# swichboard.net
KiCad netlist of a schematic drawn in EAGLE
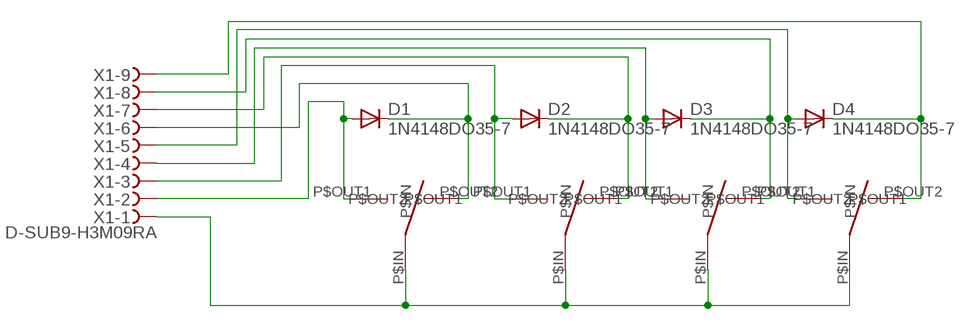
[diagram p0: schematic, sheet 1]

(export (version "E")
  (design (tool "Eeschema 10.0.6"))
  (components
    (comp (ref "D1")
      (value "1N4148DO35-7")
      (footprint "eagle-import:DO35-7")
      (libsource (lib "eagle-import") (part "1N4148DO35-7"))
    )
    (comp (ref "D2")
      (value "1N4148DO35-7")
      (footprint "eagle-import:DO35-7")
      (libsource (lib "eagle-import") (part "1N4148DO35-7"))
    )
    (comp (ref "D3")
      (value "1N4148DO35-7")
      (footprint "eagle-import:DO35-7")
      (libsource (lib "eagle-import") (part "1N4148DO35-7"))
    )
    (comp (ref "D4")
      (value "1N4148DO35-7")
      (footprint "eagle-import:DO35-7")
      (libsource (lib "eagle-import") (part "1N4148DO35-7"))
    )
    (comp (ref "U$1")
      (value "MS500E")
      (footprint "eagle-import:MS500E")
      (libsource (lib "eagle-import") (part "MS500E"))
    )
    (comp (ref "U$2")
      (value "MS500E")
      (footprint "eagle-import:MS500E")
      (libsource (lib "eagle-import") (part "MS500E"))
    )
    (comp (ref "U$3")
      (value "MS500E")
      (footprint "eagle-import:MS500E")
      (libsource (lib "eagle-import") (part "MS500E"))
    )
    (comp (ref "U$4")
      (value "MS500E")
      (footprint "eagle-import:MS500E")
      (libsource (lib "eagle-import") (part "MS500E"))
    )
    (comp (ref "X1")
      (value "D-SUB9-H3M09RA")
      (footprint "eagle-import:H3M09RA")
      (libsource (lib "eagle-import") (part "D-SUB9-H3M09RA"))
    )
  )
  (nets
    (net (code "1") (name "Net-(X1A-F)") (class "Default")
      (node (ref "U$1") (pin "P$IN") (pinfunction "P$IN_P$IN") (pintype "bidirectional"))
      (node (ref "U$2") (pin "P$IN") (pinfunction "P$IN_P$IN") (pintype "bidirectional"))
      (node (ref "U$3") (pin "P$IN") (pinfunction "P$IN_P$IN") (pintype "bidirectional"))
      (node (ref "U$4") (pin "P$IN") (pinfunction "P$IN_P$IN") (pintype "bidirectional"))
      (node (ref "X1") (pin "1") (pinfunction "F_1") (pintype "passive"))
    )
    (net (code "2") (name "Net-(X1B-F)") (class "Default")
      (node (ref "D1") (pin "A") (pinfunction "A_A") (pintype "passive"))
      (node (ref "U$1") (pin "P$OUT1") (pinfunction "P$OUT1_P$OUT1") (pintype "bidirectional"))
      (node (ref "X1") (pin "2") (pinfunction "F_2") (pintype "passive"))
    )
    (net (code "3") (name "Net-(X1C-F)") (class "Default")
      (node (ref "D2") (pin "A") (pinfunction "A_A") (pintype "passive"))
      (node (ref "U$2") (pin "P$OUT1") (pinfunction "P$OUT1_P$OUT1") (pintype "bidirectional"))
      (node (ref "X1") (pin "3") (pinfunction "F_3") (pintype "passive"))
    )
    (net (code "4") (name "Net-(X1D-F)") (class "Default")
      (node (ref "D3") (pin "A") (pinfunction "A_A") (pintype "passive"))
      (node (ref "U$3") (pin "P$OUT1") (pinfunction "P$OUT1_P$OUT1") (pintype "bidirectional"))
      (node (ref "X1") (pin "4") (pinfunction "F_4") (pintype "passive"))
    )
    (net (code "5") (name "Net-(X1E-F)") (class "Default")
      (node (ref "D4") (pin "A") (pinfunction "A_A") (pintype "passive"))
      (node (ref "U$4") (pin "P$OUT1") (pinfunction "P$OUT1_P$OUT1") (pintype "bidirectional"))
      (node (ref "X1") (pin "5") (pinfunction "F_5") (pintype "passive"))
    )
    (net (code "6") (name "Net-(X1F-F)") (class "Default")
      (node (ref "D1") (pin "C") (pinfunction "C_C") (pintype "passive"))
      (node (ref "U$1") (pin "P$OUT2") (pinfunction "P$OUT2_P$OUT2") (pintype "bidirectional"))
      (node (ref "X1") (pin "6") (pinfunction "F_6") (pintype "passive"))
    )
    (net (code "7") (name "Net-(X1G-F)") (class "Default")
      (node (ref "D2") (pin "C") (pinfunction "C_C") (pintype "passive"))
      (node (ref "U$2") (pin "P$OUT2") (pinfunction "P$OUT2_P$OUT2") (pintype "bidirectional"))
      (node (ref "X1") (pin "7") (pinfunction "F_7") (pintype "passive"))
    )
    (net (code "8") (name "Net-(X1H-F)") (class "Default")
      (node (ref "D3") (pin "C") (pinfunction "C_C") (pintype "passive"))
      (node (ref "U$3") (pin "P$OUT2") (pinfunction "P$OUT2_P$OUT2") (pintype "bidirectional"))
      (node (ref "X1") (pin "8") (pinfunction "F_8") (pintype "passive"))
    )
    (net (code "9") (name "Net-(X1I-F)") (class "Default")
      (node (ref "D4") (pin "C") (pinfunction "C_C") (pintype "passive"))
      (node (ref "U$4") (pin "P$OUT2") (pinfunction "P$OUT2_P$OUT2") (pintype "bidirectional"))
      (node (ref "X1") (pin "9") (pinfunction "F_9") (pintype "passive"))
    )
  )
)
